# psas_c3_team05.net
KiCad netlist of a schematic drawn in EAGLE
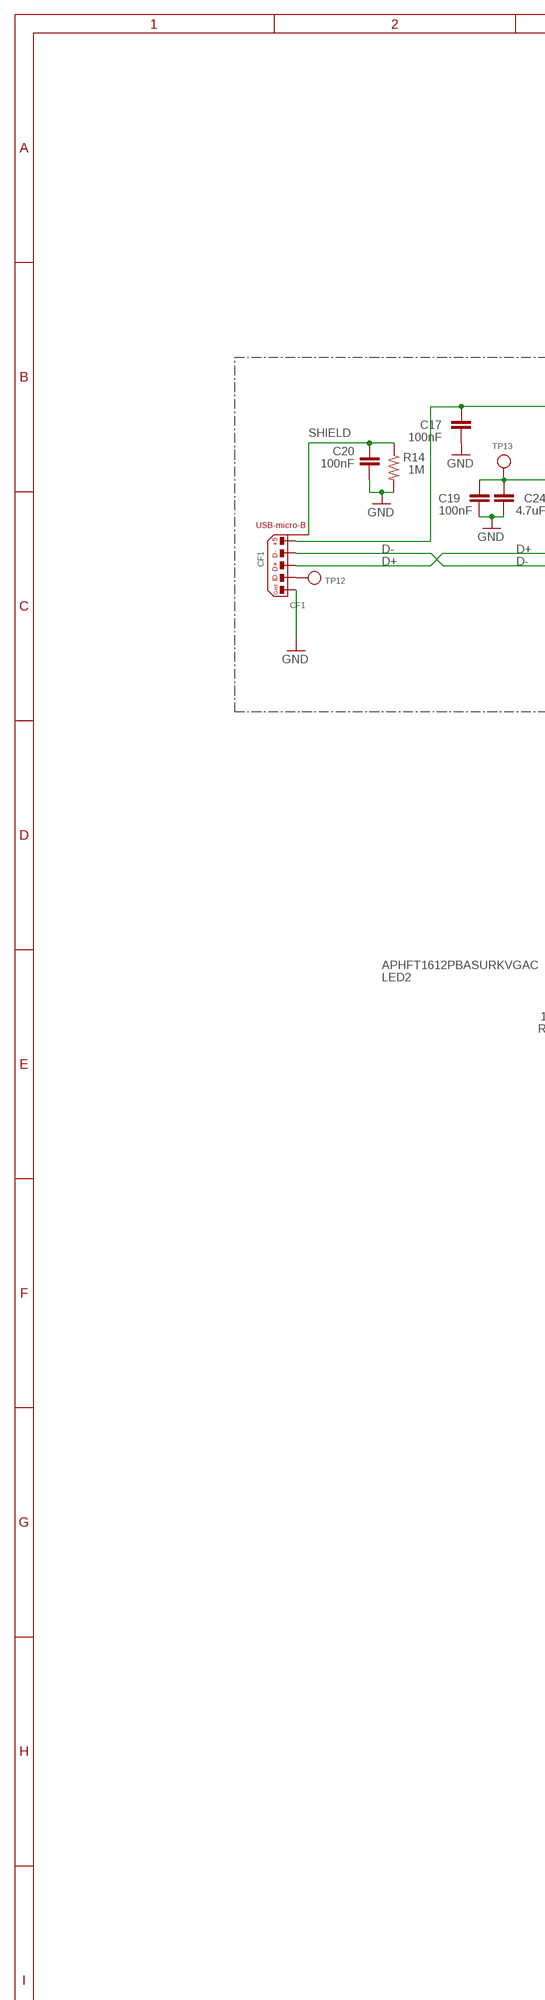
[diagram p0: schematic, sheet 1, part 1 of 2]
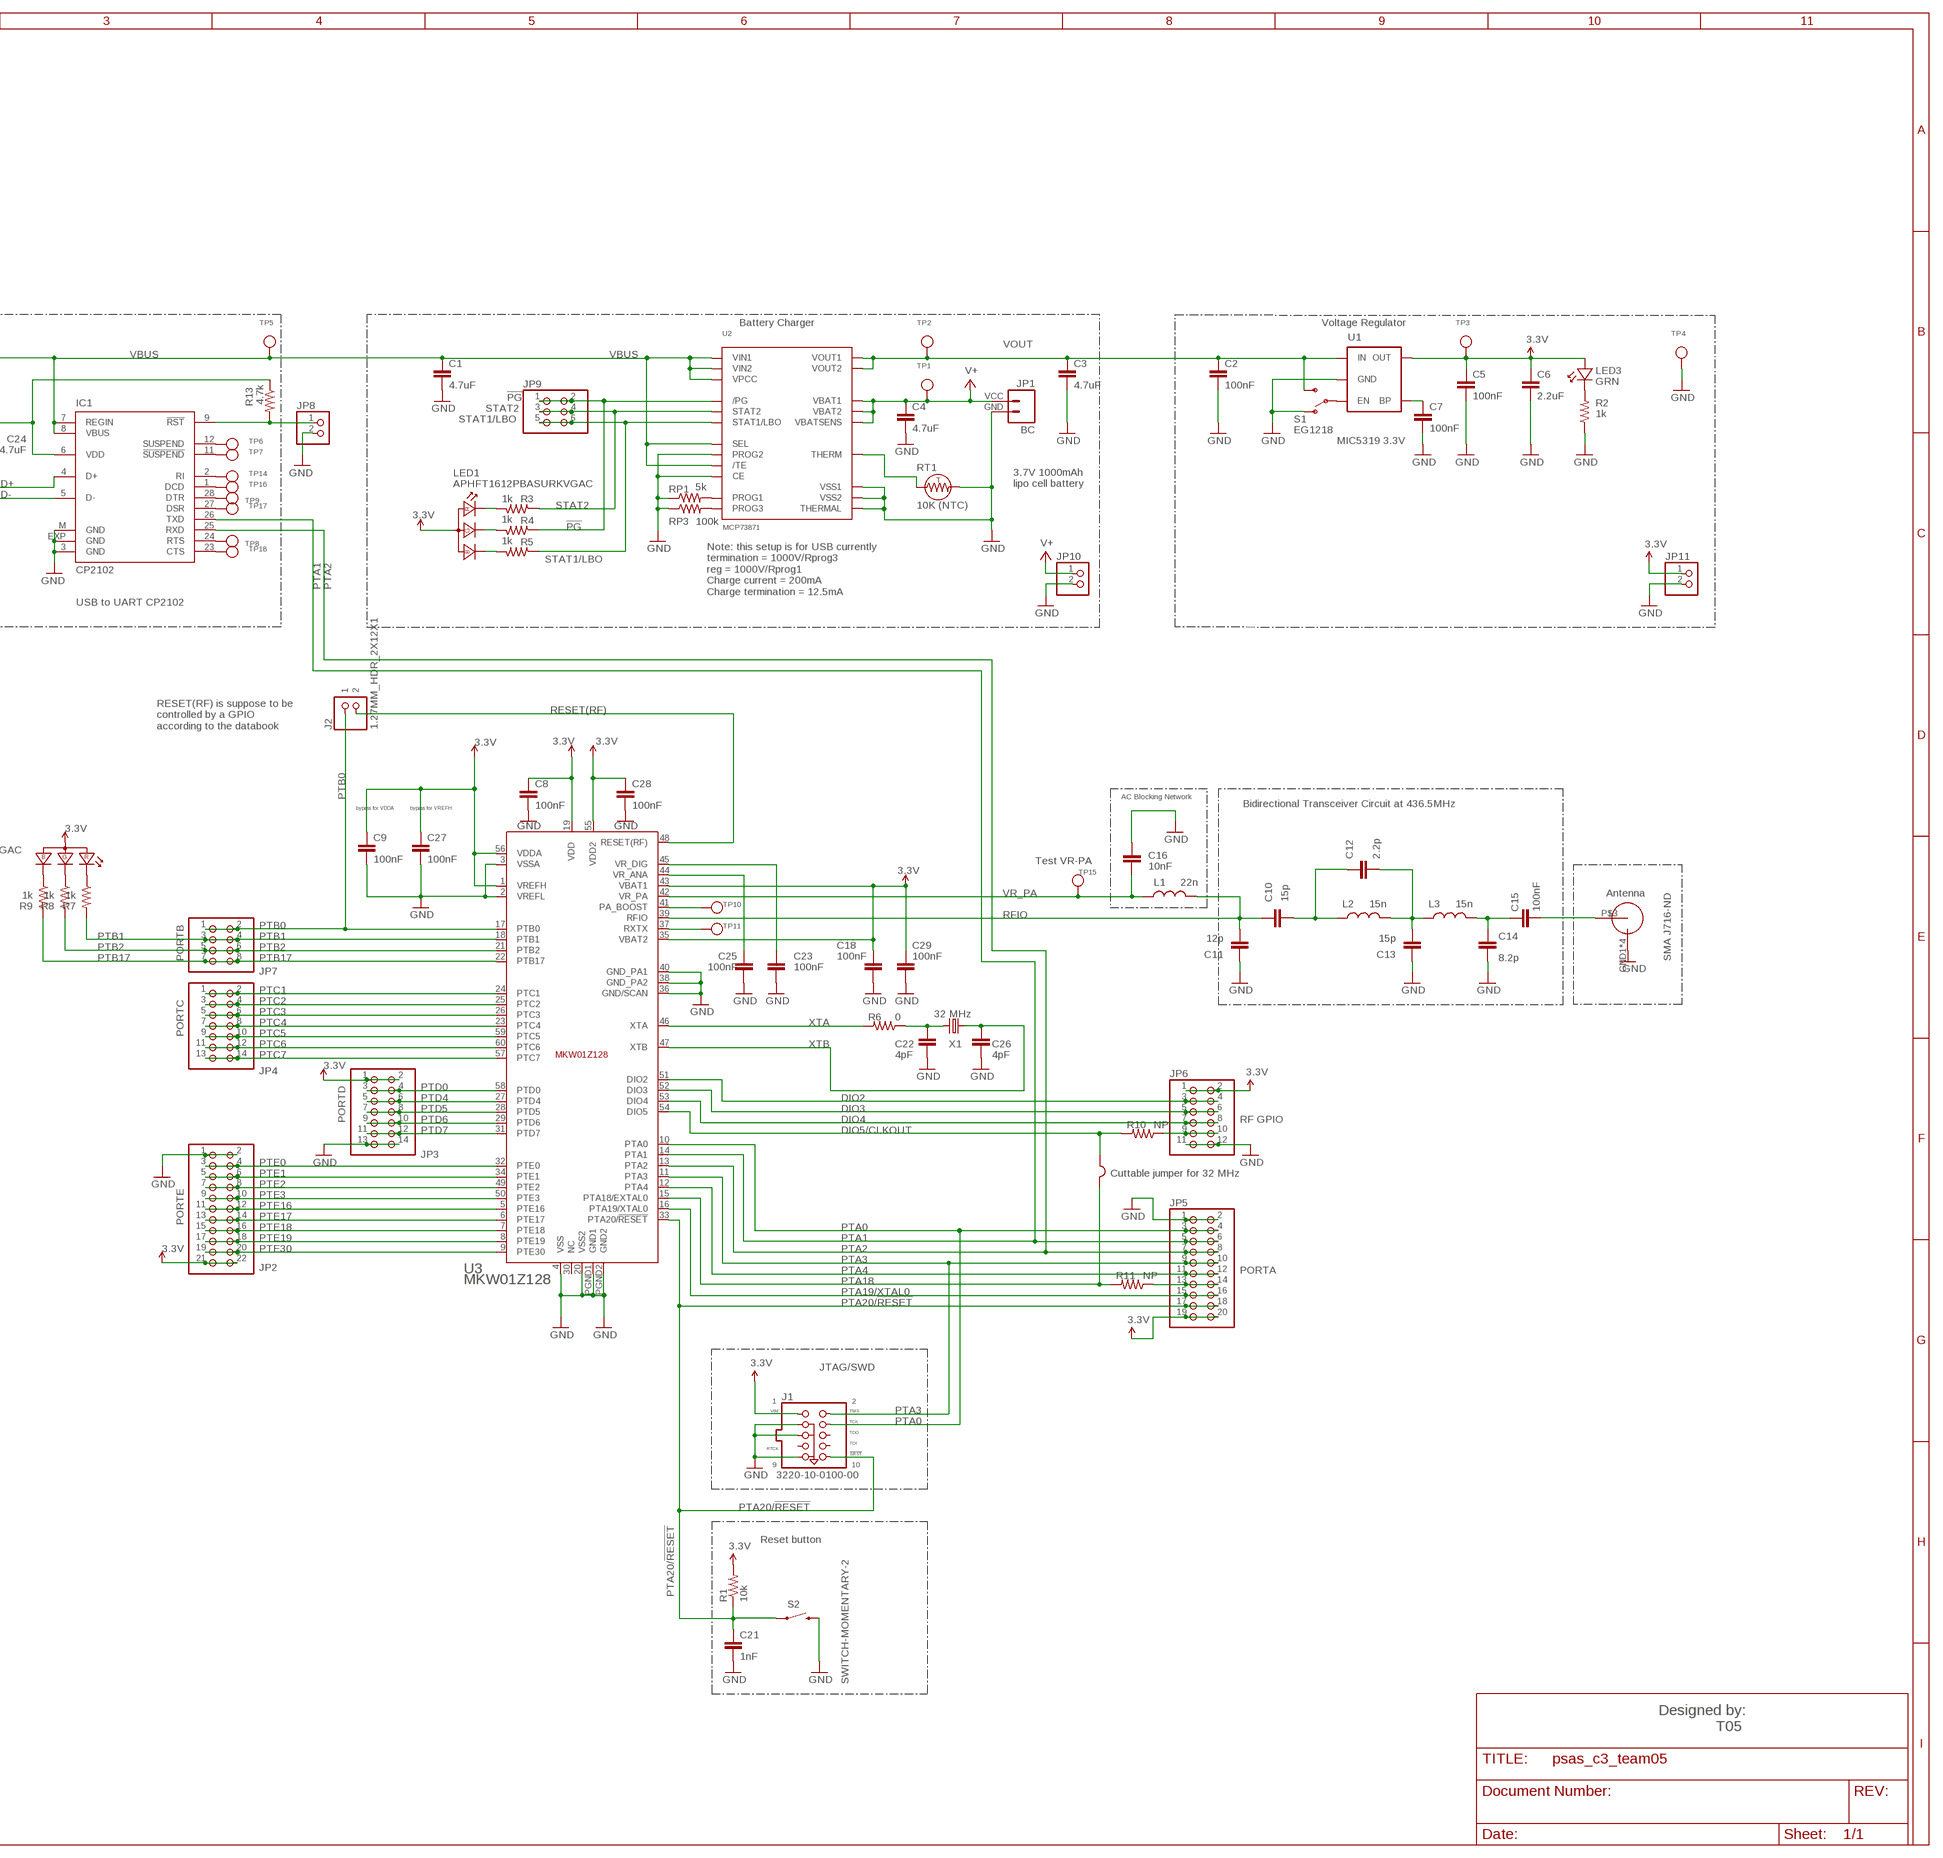
[diagram p1: schematic, sheet 1, part 2 of 2]

(export (version "E")
  (design (tool "Eeschema 10.0.6"))
  (components
    (comp (ref "C1")
      (value "4.7uF")
      (footprint "eagle-import:.0805-B-NOSILK")
      (fields (field (name "MFG") "Wurth Electronics Inc"))
      (libsource (lib "eagle-import") (part "rcl_custom_C-EU0805-B-NOSILK"))
    )
    (comp (ref "C2")
      (value "100nF")
      (footprint "eagle-import:.0603-B-NOSILK")
      (fields (field (name "MFG") "Murata Electronics North America"))
      (libsource (lib "eagle-import") (part "rcl_custom_C-EU0603-B-NOSILK"))
    )
    (comp (ref "C3")
      (value "4.7uF")
      (footprint "eagle-import:.0805-B-NOSILK")
      (fields (field (name "MFG") "Wurth Electronics Inc"))
      (libsource (lib "eagle-import") (part "rcl_custom_C-EU0805-B-NOSILK"))
    )
    (comp (ref "C4")
      (value "4.7uF")
      (footprint "eagle-import:.0805-B-NOSILK")
      (fields (field (name "MFG") "Wurth Electronics Inc"))
      (libsource (lib "eagle-import") (part "rcl_custom_C-EU0805-B-NOSILK"))
    )
    (comp (ref "C5")
      (value "100nF")
      (footprint "eagle-import:.0603-B-NOSILK")
      (fields (field (name "MFG") "Murata Electronics North America"))
      (libsource (lib "eagle-import") (part "rcl_custom_C-EU0603-B-NOSILK"))
    )
    (comp (ref "C6")
      (value "2.2uF")
      (footprint "eagle-import:.0805-B-NOSILK")
      (fields (field (name "MFG") "Murata Electronics North America"))
      (libsource (lib "eagle-import") (part "rcl_custom_C-EU0805-B-NOSILK"))
    )
    (comp (ref "C7")
      (value "100nF")
      (footprint "eagle-import:.0603-B-NOSILK")
      (fields (field (name "MFG") "Murata Electronics North America"))
      (libsource (lib "eagle-import") (part "rcl_custom_C-EU0603-B-NOSILK"))
    )
    (comp (ref "C8")
      (value "100nF")
      (footprint "eagle-import:.0603-B-NOSILK")
      (fields
        (field (name "MFG") "Murata Electronics North America")
        (field (name "MPN") "GRM188R71C104KA01D")
      )
      (libsource (lib "eagle-import") (part "C-EU0603-B-NOSILK"))
    )
    (comp (ref "C9")
      (value "100nF")
      (footprint "eagle-import:.0603-B-NOSILK")
      (fields
        (field (name "MFG") "Murata Electronics North America")
        (field (name "MPN") "GRM188R71C104KA01D")
      )
      (libsource (lib "eagle-import") (part "C-EU0603-B-NOSILK"))
    )
    (comp (ref "C10")
      (value "15p")
      (footprint "eagle-import:.0603-B-NOSILK")
      (fields (field (name "MFG") "AVX"))
      (libsource (lib "eagle-import") (part "rcl_custom_C-EU0603-B-NOSILK"))
    )
    (comp (ref "C11")
      (value "12p")
      (footprint "eagle-import:.0603-B-NOSILK")
      (fields (field (name "MFG") "AVX"))
      (libsource (lib "eagle-import") (part "rcl_custom_C-EU0603-B-NOSILK"))
    )
    (comp (ref "C12")
      (value "2.2p")
      (footprint "eagle-import:.0603-B-NOSILK")
      (fields (field (name "MFG") "Vishay / Vitramon"))
      (libsource (lib "eagle-import") (part "rcl_custom_C-EU0603-B-NOSILK"))
    )
    (comp (ref "C13")
      (value "15p")
      (footprint "eagle-import:.0603-B-NOSILK")
      (fields (field (name "MFG") "AVX"))
      (libsource (lib "eagle-import") (part "rcl_custom_C-EU0603-B-NOSILK"))
    )
    (comp (ref "C14")
      (value "8.2p")
      (footprint "eagle-import:.0603-B-NOSILK")
      (fields (field (name "MFG") "Johanson Technology"))
      (libsource (lib "eagle-import") (part "rcl_custom_C-EU0603-B-NOSILK"))
    )
    (comp (ref "C15")
      (value "100nF")
      (footprint "eagle-import:.0603-B-NOSILK")
      (fields (field (name "MFG") "AVX"))
      (libsource (lib "eagle-import") (part "rcl_custom_C-EU0603-B-NOSILK"))
    )
    (comp (ref "C16")
      (value "10nF")
      (footprint "eagle-import:.0603-B-NOSILK")
      (fields (field (name "MFG") "AVX"))
      (libsource (lib "eagle-import") (part "rcl_custom_C-EU0603-B-NOSILK"))
    )
    (comp (ref "C17")
      (value "100nF")
      (footprint "eagle-import:.0603-B-NOSILK")
      (fields (field (name "MFG") "Murata Electronics North America"))
      (libsource (lib "eagle-import") (part "rcl_custom_C-EU0603-B-NOSILK"))
    )
    (comp (ref "C18")
      (value "100nF")
      (footprint "eagle-import:.0603-B-NOSILK")
      (fields
        (field (name "MFG") "Murata Electronics North America")
        (field (name "MPN") "GRM188R71C104KA01D")
      )
      (libsource (lib "eagle-import") (part "C-EU0603-B-NOSILK"))
    )
    (comp (ref "C19")
      (value "100nF")
      (footprint "eagle-import:.0603-B-NOSILK")
      (fields (field (name "MFG") "Murata Electronics North America"))
      (libsource (lib "eagle-import") (part "rcl_custom_C-EU0603-B-NOSILK"))
    )
    (comp (ref "C20")
      (value "100nF")
      (footprint "eagle-import:.0603-B-NOSILK")
      (fields (field (name "MFG") "Murata Electronics North America"))
      (libsource (lib "eagle-import") (part "rcl_custom_C-EU0603-B-NOSILK"))
    )
    (comp (ref "C21")
      (value "1nF")
      (footprint "eagle-import:.0603-B-NOSILK")
      (fields (field (name "MFG") "Kemet"))
      (libsource (lib "eagle-import") (part "rcl_custom_C-EU0603-B-NOSILK"))
    )
    (comp (ref "C22")
      (value "4pF")
      (footprint "eagle-import:.0603-B-NOSILK")
      (fields
        (field (name "MFG") "Murata Electronics North America")
        (field (name "MPN") "GRM1885C1H4R0CA01D")
      )
      (libsource (lib "eagle-import") (part "C-EU0603-B-NOSILK"))
    )
    (comp (ref "C23")
      (value "100nF")
      (footprint "eagle-import:.0603-B-NOSILK")
      (fields
        (field (name "MFG") "Murata Electronics North America")
        (field (name "MPN") "GRM188R71C104KA01D")
      )
      (libsource (lib "eagle-import") (part "C-EU0603-B-NOSILK"))
    )
    (comp (ref "C24")
      (value "4.7uF")
      (footprint "eagle-import:.0805-B-NOSILK")
      (fields (field (name "MFG") "Wurth Electronics Inc"))
      (libsource (lib "eagle-import") (part "rcl_custom_C-EU0805-B-NOSILK"))
    )
    (comp (ref "C25")
      (value "100nF")
      (footprint "eagle-import:.0603-B-NOSILK")
      (fields
        (field (name "MFG") "Murata Electronics North America")
        (field (name "MPN") "GRM188R71C104KA01D")
      )
      (libsource (lib "eagle-import") (part "C-EU0603-B-NOSILK"))
    )
    (comp (ref "C26")
      (value "4pF")
      (footprint "eagle-import:.0603-B-NOSILK")
      (fields
        (field (name "MFG") "Murata Electronics North America")
        (field (name "MPN") "GRM1885C1H4R0CA01D")
      )
      (libsource (lib "eagle-import") (part "C-EU0603-B-NOSILK"))
    )
    (comp (ref "C27")
      (value "100nF")
      (footprint "eagle-import:.0603-B-NOSILK")
      (fields
        (field (name "MFG") "Murata Electronics North America")
        (field (name "MPN") "GRM188R71C104KA01D")
      )
      (libsource (lib "eagle-import") (part "C-EU0603-B-NOSILK"))
    )
    (comp (ref "C28")
      (value "100nF")
      (footprint "eagle-import:.0603-B-NOSILK")
      (fields
        (field (name "MFG") "Murata Electronics North America")
        (field (name "MPN") "GRM188R71C104KA01D")
      )
      (libsource (lib "eagle-import") (part "C-EU0603-B-NOSILK"))
    )
    (comp (ref "C29")
      (value "100nF")
      (footprint "eagle-import:.0603-B-NOSILK")
      (fields
        (field (name "MFG") "Murata Electronics North America")
        (field (name "MPN") "GRM188R71C104KA01D")
      )
      (libsource (lib "eagle-import") (part "C-EU0603-B-NOSILK"))
    )
    (comp (ref "CF1")
      (value "CF1")
      (footprint "eagle-import:USB-MICRO-B-PTH-HIROSE")
      (fields (field (name "MFG") "Hirose Electric Co Ltd"))
      (libsource (lib "eagle-import") (part "CON_USB-MICRO-B-RECEPTACLE-PTH-HIROSE-ZX62D-B-5P8"))
    )
    (comp (ref "IC1")
      (value "CP2102")
      (footprint "eagle-import:MLP28")
      (fields
        (field (name "MF") "FARNELL")
        (field (name "MPN") "CP2102-GM")
        (field (name "MFG") "Silicon Labs")
      )
      (libsource (lib "eagle-import") (part "CP2102"))
    )
    (comp (ref "J1")
      (value "3220-10-0100-00")
      (footprint "eagle-import:PINHEADER-2X5-0.05+POL+SILK")
      (fields (field (name "MFG") "CNC Tech"))
      (libsource (lib "eagle-import") (part "JTAG_ARM-10-50MIL"))
    )
    (comp (ref "J2")
      (value "1.27MM_HDR_2X12X1")
      (footprint "eagle-import:1.27MM_2X1")
      (libsource (lib "eagle-import") (part "1.27MM_HDR_2X12X1"))
    )
    (comp (ref "JP1")
      (value "BC")
      (footprint "eagle-import:SPARKFUN-CONNECTORS_JST-2-SMD-VERT")
      (fields (field (name "MFG") "JST Sales America Inc."))
      (libsource (lib "eagle-import") (part "SPARKFUN-CONNECTORS_M024UCON-15767"))
    )
    (comp (ref "JP2")
      (value "PINHD-2X11")
      (footprint "eagle-import:2X11")
      (libsource (lib "eagle-import") (part "PINHD-2X11"))
    )
    (comp (ref "JP3")
      (value "PINHD-2X7")
      (footprint "eagle-import:2X07")
      (libsource (lib "eagle-import") (part "PINHD-2X7"))
    )
    (comp (ref "JP4")
      (value "PINHD-2X7")
      (footprint "eagle-import:2X07")
      (libsource (lib "eagle-import") (part "PINHD-2X7"))
    )
    (comp (ref "JP5")
      (value "PINHD-2X10")
      (footprint "eagle-import:2X10")
      (libsource (lib "eagle-import") (part "PINHD-2X10"))
    )
    (comp (ref "JP6")
      (value "PINHD-2X6")
      (footprint "eagle-import:2X06")
      (libsource (lib "eagle-import") (part "PINHD-2X6"))
    )
    (comp (ref "JP7")
      (value "PINHD-2X4")
      (footprint "eagle-import:2X04")
      (libsource (lib "eagle-import") (part "PINHD-2X4"))
    )
    (comp (ref "JP8")
      (value "PINHD-1X2")
      (footprint "eagle-import:1X02")
      (libsource (lib "eagle-import") (part "PINHD-1X2"))
    )
    (comp (ref "JP9")
      (value "PINHD-2X3")
      (footprint "eagle-import:2X03")
      (libsource (lib "eagle-import") (part "PINHD-2X3"))
    )
    (comp (ref "JP10")
      (value "PINHD-1X2")
      (footprint "eagle-import:1X02")
      (libsource (lib "eagle-import") (part "PINHD-1X2"))
    )
    (comp (ref "JP11")
      (value "PINHD-1X2")
      (footprint "eagle-import:1X02")
      (libsource (lib "eagle-import") (part "PINHD-1X2"))
    )
    (comp (ref "L1")
      (value "22n")
      (footprint "eagle-import:.0603-B-NOSILK")
      (fields (field (name "MFG") "Murata"))
      (libsource (lib "eagle-import") (part "L-US0603-B-NOSILK"))
    )
    (comp (ref "L2")
      (value "15n")
      (footprint "eagle-import:.0603-B-NOSILK")
      (fields (field (name "MFG") "Murata"))
      (libsource (lib "eagle-import") (part "L-US0603-B-NOSILK"))
    )
    (comp (ref "L3")
      (value "15n")
      (footprint "eagle-import:.0603-B-NOSILK")
      (fields (field (name "MFG") "Murata"))
      (libsource (lib "eagle-import") (part "L-US0603-B-NOSILK"))
    )
    (comp (ref "LED1")
      (value "APHFT1612PBASURKVGAC")
      (footprint "eagle-import:KINGBRITE_RGBLED_1.6X1.26")
      (fields (field (name "MFG") "Lite-On Inc."))
      (libsource (lib "eagle-import") (part "LED_RGB_COMMON_ANODE-1.6X1.26"))
    )
    (comp (ref "LED2")
      (value "APHFT1612PBASURKVGAC")
      (footprint "eagle-import:KINGBRITE_RGBLED_1.6X1.26")
      (fields (field (name "MFG") "Lite-On Inc."))
      (libsource (lib "eagle-import") (part "LED_RGB_COMMON_ANODE-1.6X1.26"))
    )
    (comp (ref "LED3")
      (value "GRN")
      (footprint "eagle-import:LED-0603")
      (fields (field (name "MFG") "Lite-On Inc."))
      (libsource (lib "eagle-import") (part "LED-0603"))
    )
    (comp (ref "R1")
      (value "10k")
      (footprint "eagle-import:.0603-B-NOSILK")
      (fields (field (name "MFG") "Yageo"))
      (libsource (lib "eagle-import") (part "R-US_0603-B-NOSILK"))
    )
    (comp (ref "R2")
      (value "1k")
      (footprint "eagle-import:.0603-B-NOSILK")
      (fields (field (name "MFG") "Yageo"))
      (libsource (lib "eagle-import") (part "R-US_0603-B-NOSILK"))
    )
    (comp (ref "R3")
      (value "1k")
      (footprint "eagle-import:.0603-B-NOSILK")
      (fields (field (name "MFG") "Yageo"))
      (libsource (lib "eagle-import") (part "R-US_0603-B-NOSILK"))
    )
    (comp (ref "R4")
      (value "1k")
      (footprint "eagle-import:.0603-B-NOSILK")
      (fields (field (name "MFG") "Yageo"))
      (libsource (lib "eagle-import") (part "R-US_0603-B-NOSILK"))
    )
    (comp (ref "R5")
      (value "1k")
      (footprint "eagle-import:.0603-B-NOSILK")
      (fields (field (name "MFG") "Yageo"))
      (libsource (lib "eagle-import") (part "R-US_0603-B-NOSILK"))
    )
    (comp (ref "R6")
      (value "0")
      (footprint "eagle-import:.0603-B-NOSILK")
      (libsource (lib "eagle-import") (part "R-US_0603-B-NOSILK"))
    )
    (comp (ref "R7")
      (value "1k")
      (footprint "eagle-import:.0603-B-NOSILK")
      (fields (field (name "MFG") "Yageo"))
      (libsource (lib "eagle-import") (part "R-US_0603-B-NOSILK"))
    )
    (comp (ref "R8")
      (value "1k")
      (footprint "eagle-import:.0603-B-NOSILK")
      (fields (field (name "MFG") "Yageo"))
      (libsource (lib "eagle-import") (part "R-US_0603-B-NOSILK"))
    )
    (comp (ref "R9")
      (value "1k")
      (footprint "eagle-import:.0603-B-NOSILK")
      (fields (field (name "MFG") "Yageo"))
      (libsource (lib "eagle-import") (part "R-US_0603-B-NOSILK"))
    )
    (comp (ref "R10")
      (value "NP")
      (footprint "eagle-import:.0603-B-NOSILK")
      (libsource (lib "eagle-import") (part "R-US_0603-B-NOSILK"))
    )
    (comp (ref "R11")
      (value "NP")
      (footprint "eagle-import:.0603-B-NOSILK")
      (libsource (lib "eagle-import") (part "R-US_0603-B-NOSILK"))
    )
    (comp (ref "R13")
      (value "4.7k")
      (footprint "eagle-import:.0603-B-NOSILK")
      (fields (field (name "MFG") "Yageo"))
      (libsource (lib "eagle-import") (part "R-US_0603-B-NOSILK"))
    )
    (comp (ref "R14")
      (value "1M")
      (footprint "eagle-import:.0603-B-NOSILK")
      (fields (field (name "MFG") "Yageo"))
      (libsource (lib "eagle-import") (part "R-US_0603-B-NOSILK"))
    )
    (comp (ref "RP1")
      (value "5k")
      (footprint "eagle-import:.0603-B-NOSILK")
      (fields (field (name "MFG") "Yageo"))
      (libsource (lib "eagle-import") (part "R-US_0603-B-NOSILK"))
    )
    (comp (ref "RP3")
      (value "100k")
      (footprint "eagle-import:.0603-B-NOSILK")
      (fields (field (name "MFG") "Yageo"))
      (libsource (lib "eagle-import") (part "R-US_0603-B-NOSILK"))
    )
    (comp (ref "RT1")
      (value "10K (NTC)")
      (footprint "eagle-import:R1206")
      (fields (field (name "MFG") "Honeywell Sensing and Control"))
      (libsource (lib "eagle-import") (part "THERMISTOR-_1206"))
    )
    (comp (ref "S1")
      (value "EG1218")
      (footprint "eagle-import:SWITCH-SPDT")
      (fields (field (name "MFG") "E-Switch"))
      (libsource (lib "eagle-import") (part "SWITCH-SPSTPTH"))
    )
    (comp (ref "S2")
      (value "SWITCH-MOMENTARY-2")
      (footprint "eagle-import:TACTILE_SWITCH_TALL")
      (fields (field (name "MFG") "TE Connectivity Alcoswitch Switches"))
      (libsource (lib "eagle-import") (part "SWITCH-MOMENTARY-2"))
    )
    (comp (ref "TP1")
      (value "TESTPOINTROUND0.5MM")
      (footprint "eagle-import:TESTPOINT_ROUND_0.5MM")
      (libsource (lib "eagle-import") (part "TESTPOINTROUND0.5MM"))
    )
    (comp (ref "TP2")
      (value "TESTPOINTROUND0.5MM")
      (footprint "eagle-import:TESTPOINT_ROUND_0.5MM")
      (libsource (lib "eagle-import") (part "TESTPOINTROUND0.5MM"))
    )
    (comp (ref "TP3")
      (value "TESTPOINTROUND0.5MM")
      (footprint "eagle-import:TESTPOINT_ROUND_0.5MM")
      (libsource (lib "eagle-import") (part "TESTPOINTROUND0.5MM"))
    )
    (comp (ref "TP4")
      (value "TESTPOINTROUND0.5MM")
      (footprint "eagle-import:TESTPOINT_ROUND_0.5MM")
      (libsource (lib "eagle-import") (part "TESTPOINTROUND0.5MM"))
    )
    (comp (ref "TP5")
      (value "TESTPOINTROUND0.5MM")
      (footprint "eagle-import:TESTPOINT_ROUND_0.5MM")
      (libsource (lib "eagle-import") (part "TESTPOINTROUND0.5MM"))
    )
    (comp (ref "TP6")
      (value "TESTPOINTROUND0.5MM")
      (footprint "eagle-import:TESTPOINT_ROUND_0.5MM")
      (libsource (lib "eagle-import") (part "TESTPOINTROUND0.5MM"))
    )
    (comp (ref "TP7")
      (value "TESTPOINTROUND0.5MM")
      (footprint "eagle-import:TESTPOINT_ROUND_0.5MM")
      (libsource (lib "eagle-import") (part "TESTPOINTROUND0.5MM"))
    )
    (comp (ref "TP8")
      (value "TESTPOINTROUND0.5MM")
      (footprint "eagle-import:TESTPOINT_ROUND_0.5MM")
      (libsource (lib "eagle-import") (part "TESTPOINTROUND0.5MM"))
    )
    (comp (ref "TP9")
      (value "TESTPOINTROUND0.5MM")
      (footprint "eagle-import:TESTPOINT_ROUND_0.5MM")
      (libsource (lib "eagle-import") (part "TESTPOINTROUND0.5MM"))
    )
    (comp (ref "TP10")
      (value "TESTPOINTROUND0.5MM")
      (footprint "eagle-import:TESTPOINT_ROUND_0.5MM")
      (libsource (lib "eagle-import") (part "TESTPOINTROUND0.5MM"))
    )
    (comp (ref "TP11")
      (value "TESTPOINTROUND0.5MM")
      (footprint "eagle-import:TESTPOINT_ROUND_0.5MM")
      (libsource (lib "eagle-import") (part "TESTPOINTROUND0.5MM"))
    )
    (comp (ref "TP12")
      (value "TESTPOINTROUND0.5MM")
      (footprint "eagle-import:TESTPOINT_ROUND_0.5MM")
      (libsource (lib "eagle-import") (part "TESTPOINTROUND0.5MM"))
    )
    (comp (ref "TP13")
      (value "TESTPOINTROUND0.5MM")
      (footprint "eagle-import:TESTPOINT_ROUND_0.5MM")
      (libsource (lib "eagle-import") (part "TESTPOINTROUND0.5MM"))
    )
    (comp (ref "TP14")
      (value "TESTPOINTROUND0.5MM")
      (footprint "eagle-import:TESTPOINT_ROUND_0.5MM")
      (libsource (lib "eagle-import") (part "TESTPOINTROUND0.5MM"))
    )
    (comp (ref "TP15")
      (value "TESTPOINTROUND0.5MM")
      (footprint "eagle-import:TESTPOINT_ROUND_0.5MM")
      (libsource (lib "eagle-import") (part "TESTPOINTROUND0.5MM"))
    )
    (comp (ref "TP16")
      (value "TESTPOINTROUND0.5MM")
      (footprint "eagle-import:TESTPOINT_ROUND_0.5MM")
      (libsource (lib "eagle-import") (part "TESTPOINTROUND0.5MM"))
    )
    (comp (ref "TP17")
      (value "TESTPOINTROUND0.5MM")
      (footprint "eagle-import:TESTPOINT_ROUND_0.5MM")
      (libsource (lib "eagle-import") (part "TESTPOINTROUND0.5MM"))
    )
    (comp (ref "TP18")
      (value "TESTPOINTROUND0.5MM")
      (footprint "eagle-import:TESTPOINT_ROUND_0.5MM")
      (libsource (lib "eagle-import") (part "TESTPOINTROUND0.5MM"))
    )
    (comp (ref "U$2")
      (value "SMAJ716-ND")
      (footprint "eagle-import:SMAJ716-ND")
      (fields (field (name "MFG") "Cinch Connectivity Solutions"))
      (libsource (lib "eagle-import") (part "SMAJ716-ND"))
    )
    (comp (ref "U1")
      (value "MIC5319 3.3V")
      (footprint "eagle-import:SPARKFUN-POWERIC_SOT23-5")
      (fields (field (name "MFG") "Microchip Technology"))
      (libsource (lib "eagle-import") (part "SPARKFUN-POWERIC_V_REG_MIC52193.3V"))
    )
    (comp (ref "U2")
      (value "MCP73871")
      (footprint "eagle-import:QFN20_4MM")
      (fields (field (name "MFG") "Microchip Technology"))
      (libsource (lib "eagle-import") (part "MCP73871"))
    )
    (comp (ref "U3")
      (value "MKW01Z128")
      (footprint "eagle-import:MKW01Z128")
      (fields (field (name "MFG") "Freescale Semiconductor"))
      (libsource (lib "eagle-import") (part "MKW01Z128"))
    )
    (comp (ref "W1")
      (value "CONNECTION-0.4")
      (footprint "eagle-import:CONNECTION-BUTT-0.4")
      (libsource (lib "eagle-import") (part "CONNECTION-0.4"))
    )
    (comp (ref "X1")
      (value "32 MHz")
      (footprint "eagle-import:FC-12M")
      (fields (field (name "MFG") "AVX Corp/Kyocera Corp"))
      (libsource (lib "eagle-import") (part "FC-12M"))
    )
  )
  (nets
    (net (code "1") (name "/D+") (class "Default")
      (node (ref "CF1") (pin "3") (pinfunction "3_3") (pintype "passive"))
      (node (ref "IC1") (pin "4") (pinfunction "D+_4") (pintype "bidirectional"))
    )
    (net (code "2") (name "/D-") (class "Default")
      (node (ref "CF1") (pin "2") (pinfunction "2_2") (pintype "passive"))
      (node (ref "IC1") (pin "5") (pinfunction "D-_5") (pintype "bidirectional"))
    )
    (net (code "3") (name "/DIO2") (class "Default")
      (node (ref "JP6") (pin "3") (pinfunction "3_3") (pintype "passive"))
      (node (ref "JP6") (pin "4") (pinfunction "4_4") (pintype "passive"))
      (node (ref "U3") (pin "51") (pinfunction "DIO2_51") (pintype "bidirectional"))
    )
    (net (code "4") (name "/DIO3") (class "Default")
      (node (ref "JP6") (pin "5") (pinfunction "5_5") (pintype "passive"))
      (node (ref "JP6") (pin "6") (pinfunction "6_6") (pintype "passive"))
      (node (ref "U3") (pin "52") (pinfunction "DIO3_52") (pintype "bidirectional"))
    )
    (net (code "5") (name "/DIO4") (class "Default")
      (node (ref "JP6") (pin "7") (pinfunction "7_7") (pintype "passive"))
      (node (ref "JP6") (pin "8") (pinfunction "8_8") (pintype "passive"))
      (node (ref "U3") (pin "53") (pinfunction "DIO4_53") (pintype "bidirectional"))
    )
    (net (code "6") (name "/DIO5{slash}CLKOUT") (class "Default")
      (node (ref "R10") (pin "2") (pinfunction "2_2") (pintype "passive"))
      (node (ref "U3") (pin "54") (pinfunction "DIO5_54") (pintype "bidirectional"))
      (node (ref "W1") (pin "P1") (pinfunction "1_P1") (pintype "passive"))
    )
    (net (code "7") (name "/PTA0") (class "Default")
      (node (ref "J1") (pin "4") (pinfunction "TCK_4") (pintype "passive"))
      (node (ref "JP5") (pin "3") (pinfunction "3_3") (pintype "passive"))
      (node (ref "JP5") (pin "4") (pinfunction "4_4") (pintype "passive"))
      (node (ref "U3") (pin "10") (pinfunction "PTA0_10") (pintype "bidirectional"))
    )
    (net (code "8") (name "/PTA1") (class "Default")
      (node (ref "IC1") (pin "26") (pinfunction "TXD_26") (pintype "output"))
      (node (ref "JP5") (pin "5") (pinfunction "5_5") (pintype "passive"))
      (node (ref "JP5") (pin "6") (pinfunction "6_6") (pintype "passive"))
      (node (ref "U3") (pin "14") (pinfunction "PTA1_14") (pintype "bidirectional"))
    )
    (net (code "9") (name "/PTA2") (class "Default")
      (node (ref "IC1") (pin "25") (pinfunction "RXD_25") (pintype "input"))
      (node (ref "JP5") (pin "7") (pinfunction "7_7") (pintype "passive"))
      (node (ref "JP5") (pin "8") (pinfunction "8_8") (pintype "passive"))
      (node (ref "U3") (pin "13") (pinfunction "PTA2_13") (pintype "bidirectional"))
    )
    (net (code "10") (name "/PTA3") (class "Default")
      (node (ref "J1") (pin "2") (pinfunction "TMS_2") (pintype "passive"))
      (node (ref "JP5") (pin "10") (pinfunction "10_10") (pintype "passive"))
      (node (ref "JP5") (pin "9") (pinfunction "9_9") (pintype "passive"))
      (node (ref "U3") (pin "11") (pinfunction "PTA3_11") (pintype "bidirectional"))
    )
    (net (code "11") (name "/PTA4") (class "Default")
      (node (ref "JP5") (pin "11") (pinfunction "11_11") (pintype "passive"))
      (node (ref "JP5") (pin "12") (pinfunction "12_12") (pintype "passive"))
      (node (ref "U3") (pin "12") (pinfunction "PTA4_12") (pintype "bidirectional"))
    )
    (net (code "12") (name "/PTA18") (class "Default")
      (node (ref "R11") (pin "2") (pinfunction "2_2") (pintype "passive"))
      (node (ref "U3") (pin "15") (pinfunction "PTA18/EXTAL0_15") (pintype "bidirectional"))
      (node (ref "W1") (pin "P2") (pinfunction "2_P2") (pintype "passive"))
    )
    (net (code "13") (name "/PTA19{slash}XTAL0") (class "Default")
      (node (ref "JP5") (pin "15") (pinfunction "15_15") (pintype "passive"))
      (node (ref "JP5") (pin "16") (pinfunction "16_16") (pintype "passive"))
      (node (ref "U3") (pin "16") (pinfunction "PTA19/XTAL0_16") (pintype "bidirectional"))
    )
    (net (code "14") (name "/PTA20{slash}~{RESET}") (class "Default")
      (node (ref "C21") (pin "1") (pinfunction "1_1") (pintype "passive"))
      (node (ref "J1") (pin "10") (pinfunction "SRST_10") (pintype "passive"))
      (node (ref "JP5") (pin "17") (pinfunction "17_17") (pintype "passive"))
      (node (ref "JP5") (pin "18") (pinfunction "18_18") (pintype "passive"))
      (node (ref "R1") (pin "1") (pinfunction "1_1") (pintype "passive"))
      (node (ref "S2") (pin "A2") (pinfunction "1_A2") (pintype "passive"))
      (node (ref "U3") (pin "33") (pinfunction "PTA20/~{RESET}_33") (pintype "bidirectional"))
    )
    (net (code "15") (name "/PTB0") (class "Default")
      (node (ref "J2") (pin "1") (pinfunction "1_1") (pintype "passive"))
      (node (ref "JP7") (pin "1") (pinfunction "1_1") (pintype "passive"))
      (node (ref "JP7") (pin "2") (pinfunction "2_2") (pintype "passive"))
      (node (ref "U3") (pin "17") (pinfunction "PTB0_17") (pintype "bidirectional"))
    )
    (net (code "16") (name "/PTB1") (class "Default")
      (node (ref "JP7") (pin "3") (pinfunction "3_3") (pintype "passive"))
      (node (ref "JP7") (pin "4") (pinfunction "4_4") (pintype "passive"))
      (node (ref "R7") (pin "2") (pinfunction "2_2") (pintype "passive"))
      (node (ref "U3") (pin "18") (pinfunction "PTB1_18") (pintype "bidirectional"))
    )
    (net (code "17") (name "/PTB2") (class "Default")
      (node (ref "JP7") (pin "5") (pinfunction "5_5") (pintype "passive"))
      (node (ref "JP7") (pin "6") (pinfunction "6_6") (pintype "passive"))
      (node (ref "R8") (pin "2") (pinfunction "2_2") (pintype "passive"))
      (node (ref "U3") (pin "21") (pinfunction "PTB2_21") (pintype "bidirectional"))
    )
    (net (code "18") (name "/PTB17") (class "Default")
      (node (ref "JP7") (pin "7") (pinfunction "7_7") (pintype "passive"))
      (node (ref "JP7") (pin "8") (pinfunction "8_8") (pintype "passive"))
      (node (ref "R9") (pin "2") (pinfunction "2_2") (pintype "passive"))
      (node (ref "U3") (pin "22") (pinfunction "PTB17_22") (pintype "bidirectional"))
    )
    (net (code "19") (name "/PTC1") (class "Default")
      (node (ref "JP4") (pin "1") (pinfunction "1_1") (pintype "passive"))
      (node (ref "JP4") (pin "2") (pinfunction "2_2") (pintype "passive"))
      (node (ref "U3") (pin "24") (pinfunction "PTC1_24") (pintype "bidirectional"))
    )
    (net (code "20") (name "/PTC2") (class "Default")
      (node (ref "JP4") (pin "3") (pinfunction "3_3") (pintype "passive"))
      (node (ref "JP4") (pin "4") (pinfunction "4_4") (pintype "passive"))
      (node (ref "U3") (pin "25") (pinfunction "PTC2_25") (pintype "bidirectional"))
    )
    (net (code "21") (name "/PTC3") (class "Default")
      (node (ref "JP4") (pin "5") (pinfunction "5_5") (pintype "passive"))
      (node (ref "JP4") (pin "6") (pinfunction "6_6") (pintype "passive"))
      (node (ref "U3") (pin "26") (pinfunction "PTC3_26") (pintype "bidirectional"))
    )
    (net (code "22") (name "/PTC4") (class "Default")
      (node (ref "JP4") (pin "7") (pinfunction "7_7") (pintype "passive"))
      (node (ref "JP4") (pin "8") (pinfunction "8_8") (pintype "passive"))
      (node (ref "U3") (pin "23") (pinfunction "PTC4_23") (pintype "bidirectional"))
    )
    (net (code "23") (name "/PTC5") (class "Default")
      (node (ref "JP4") (pin "10") (pinfunction "10_10") (pintype "passive"))
      (node (ref "JP4") (pin "9") (pinfunction "9_9") (pintype "passive"))
      (node (ref "U3") (pin "59") (pinfunction "PTC5_59") (pintype "bidirectional"))
    )
    (net (code "24") (name "/PTC6") (class "Default")
      (node (ref "JP4") (pin "11") (pinfunction "11_11") (pintype "passive"))
      (node (ref "JP4") (pin "12") (pinfunction "12_12") (pintype "passive"))
      (node (ref "U3") (pin "60") (pinfunction "PTC6_60") (pintype "bidirectional"))
    )
    (net (code "25") (name "/PTC7") (class "Default")
      (node (ref "JP4") (pin "13") (pinfunction "13_13") (pintype "passive"))
      (node (ref "JP4") (pin "14") (pinfunction "14_14") (pintype "passive"))
      (node (ref "U3") (pin "57") (pinfunction "PTC7_57") (pintype "bidirectional"))
    )
    (net (code "26") (name "/PTD0") (class "Default")
      (node (ref "JP3") (pin "3") (pinfunction "3_3") (pintype "passive"))
      (node (ref "JP3") (pin "4") (pinfunction "4_4") (pintype "passive"))
      (node (ref "U3") (pin "58") (pinfunction "PTD0_58") (pintype "bidirectional"))
    )
    (net (code "27") (name "/PTD4") (class "Default")
      (node (ref "JP3") (pin "5") (pinfunction "5_5") (pintype "passive"))
      (node (ref "JP3") (pin "6") (pinfunction "6_6") (pintype "passive"))
      (node (ref "U3") (pin "27") (pinfunction "PTD4_27") (pintype "bidirectional"))
    )
    (net (code "28") (name "/PTD5") (class "Default")
      (node (ref "JP3") (pin "7") (pinfunction "7_7") (pintype "passive"))
      (node (ref "JP3") (pin "8") (pinfunction "8_8") (pintype "passive"))
      (node (ref "U3") (pin "28") (pinfunction "PTD5_28") (pintype "bidirectional"))
    )
    (net (code "29") (name "/PTD6") (class "Default")
      (node (ref "JP3") (pin "10") (pinfunction "10_10") (pintype "passive"))
      (node (ref "JP3") (pin "9") (pinfunction "9_9") (pintype "passive"))
      (node (ref "U3") (pin "29") (pinfunction "PTD6_29") (pintype "bidirectional"))
    )
    (net (code "30") (name "/PTD7") (class "Default")
      (node (ref "JP3") (pin "11") (pinfunction "11_11") (pintype "passive"))
      (node (ref "JP3") (pin "12") (pinfunction "12_12") (pintype "passive"))
      (node (ref "U3") (pin "31") (pinfunction "PTD7_31") (pintype "bidirectional"))
    )
    (net (code "31") (name "/PTE0") (class "Default")
      (node (ref "JP2") (pin "3") (pinfunction "3_3") (pintype "passive"))
      (node (ref "JP2") (pin "4") (pinfunction "4_4") (pintype "passive"))
      (node (ref "U3") (pin "32") (pinfunction "PTE0_32") (pintype "bidirectional"))
    )
    (net (code "32") (name "/PTE1") (class "Default")
      (node (ref "JP2") (pin "5") (pinfunction "5_5") (pintype "passive"))
      (node (ref "JP2") (pin "6") (pinfunction "6_6") (pintype "passive"))
      (node (ref "U3") (pin "34") (pinfunction "PTE1_34") (pintype "bidirectional"))
    )
    (net (code "33") (name "/PTE2") (class "Default")
      (node (ref "JP2") (pin "7") (pinfunction "7_7") (pintype "passive"))
      (node (ref "JP2") (pin "8") (pinfunction "8_8") (pintype "passive"))
      (node (ref "U3") (pin "49") (pinfunction "PTE2_49") (pintype "bidirectional"))
    )
    (net (code "34") (name "/PTE3") (class "Default")
      (node (ref "JP2") (pin "10") (pinfunction "10_10") (pintype "passive"))
      (node (ref "JP2") (pin "9") (pinfunction "9_9") (pintype "passive"))
      (node (ref "U3") (pin "50") (pinfunction "PTE3_50") (pintype "bidirectional"))
    )
    (net (code "35") (name "/PTE16") (class "Default")
      (node (ref "JP2") (pin "11") (pinfunction "11_11") (pintype "passive"))
      (node (ref "JP2") (pin "12") (pinfunction "12_12") (pintype "passive"))
      (node (ref "U3") (pin "5") (pinfunction "PTE16_5") (pintype "bidirectional"))
    )
    (net (code "36") (name "/PTE17") (class "Default")
      (node (ref "JP2") (pin "13") (pinfunction "13_13") (pintype "passive"))
      (node (ref "JP2") (pin "14") (pinfunction "14_14") (pintype "passive"))
      (node (ref "U3") (pin "6") (pinfunction "PTE17_6") (pintype "bidirectional"))
    )
    (net (code "37") (name "/PTE18") (class "Default")
      (node (ref "JP2") (pin "15") (pinfunction "15_15") (pintype "passive"))
      (node (ref "JP2") (pin "16") (pinfunction "16_16") (pintype "passive"))
      (node (ref "U3") (pin "7") (pinfunction "PTE18_7") (pintype "bidirectional"))
    )
    (net (code "38") (name "/PTE19") (class "Default")
      (node (ref "JP2") (pin "17") (pinfunction "17_17") (pintype "passive"))
      (node (ref "JP2") (pin "18") (pinfunction "18_18") (pintype "passive"))
      (node (ref "U3") (pin "8") (pinfunction "PTE19_8") (pintype "bidirectional"))
    )
    (net (code "39") (name "/PTE30") (class "Default")
      (node (ref "JP2") (pin "19") (pinfunction "19_19") (pintype "passive"))
      (node (ref "JP2") (pin "20") (pinfunction "20_20") (pintype "passive"))
      (node (ref "U3") (pin "9") (pinfunction "PTE30_9") (pintype "bidirectional"))
    )
    (net (code "40") (name "/RESET(RF)") (class "Default")
      (node (ref "J2") (pin "2") (pinfunction "2_2") (pintype "passive"))
      (node (ref "U3") (pin "48") (pinfunction "RESET(RF)_48") (pintype "input"))
    )
    (net (code "41") (name "/RFIO") (class "Default")
      (node (ref "C10") (pin "2") (pinfunction "2_2") (pintype "passive"))
      (node (ref "C11") (pin "1") (pinfunction "1_1") (pintype "passive"))
      (node (ref "L1") (pin "2") (pinfunction "2_2") (pintype "passive"))
      (node (ref "U3") (pin "39") (pinfunction "RFIO_39") (pintype "bidirectional"))
    )
    (net (code "42") (name "/SHIELD") (class "Default")
      (node (ref "C20") (pin "1") (pinfunction "1_1") (pintype "passive"))
      (node (ref "CF1") (pin "S1") (pinfunction "SHIELD_S1") (pintype "passive"))
      (node (ref "CF1") (pin "S2") (pinfunction "SHIELD_S2") (pintype "passive"))
      (node (ref "CF1") (pin "S3") (pinfunction "SHIELD_S3") (pintype "passive"))
      (node (ref "CF1") (pin "S4") (pinfunction "SHIELD_S4") (pintype "passive"))
      (node (ref "R14") (pin "1") (pinfunction "1_1") (pintype "passive"))
    )
    (net (code "43") (name "/STAT1{slash}LBO") (class "Default")
      (node (ref "JP9") (pin "5") (pinfunction "5_5") (pintype "passive"))
      (node (ref "JP9") (pin "6") (pinfunction "6_6") (pintype "passive"))
      (node (ref "R5") (pin "1") (pinfunction "1_1") (pintype "passive"))
      (node (ref "U2") (pin "P$8") (pinfunction "STAT1/LBO_P$8") (pintype "output"))
    )
    (net (code "44") (name "/STAT2") (class "Default")
      (node (ref "JP9") (pin "3") (pinfunction "3_3") (pintype "passive"))
      (node (ref "JP9") (pin "4") (pinfunction "4_4") (pintype "passive"))
      (node (ref "R3") (pin "1") (pinfunction "1_1") (pintype "passive"))
      (node (ref "U2") (pin "P$7") (pinfunction "STAT2_P$7") (pintype "output"))
    )
    (net (code "45") (name "/VBUS") (class "Default")
      (node (ref "C1") (pin "1") (pinfunction "1_1") (pintype "passive"))
      (node (ref "C17") (pin "1") (pinfunction "1_1") (pintype "passive"))
      (node (ref "CF1") (pin "1") (pinfunction "1_1") (pintype "passive"))
      (node (ref "IC1") (pin "7") (pinfunction "REGIN_7") (pintype "passive"))
      (node (ref "IC1") (pin "8") (pinfunction "VBUS_8") (pintype "input"))
      (node (ref "TP5") (pin "P$1") (pinfunction "P$1_P$1") (pintype "bidirectional"))
      (node (ref "U2") (pin "P$18") (pinfunction "VIN1_P$18") (pintype "power_in"))
      (node (ref "U2") (pin "P$19") (pinfunction "VIN2_P$19") (pintype "power_in"))
      (node (ref "U2") (pin "P$2") (pinfunction "VPCC_P$2") (pintype "passive"))
      (node (ref "U2") (pin "P$3") (pinfunction "SEL_P$3") (pintype "input"))
      (node (ref "U2") (pin "P$9") (pinfunction "/TE_P$9") (pintype "input"))
    )
    (net (code "46") (name "/VOUT") (class "Default")
      (node (ref "C2") (pin "1") (pinfunction "1_1") (pintype "passive"))
      (node (ref "C3") (pin "1") (pinfunction "1_1") (pintype "passive"))
      (node (ref "S1") (pin "3") (pinfunction "S_3") (pintype "passive"))
      (node (ref "TP2") (pin "P$1") (pinfunction "P$1_P$1") (pintype "bidirectional"))
      (node (ref "U1") (pin "1") (pinfunction "IN_1") (pintype "input"))
      (node (ref "U2") (pin "P$1") (pinfunction "VOUT1_P$1") (pintype "power_in"))
      (node (ref "U2") (pin "P$20") (pinfunction "VOUT2_P$20") (pintype "power_in"))
    )
    (net (code "47") (name "/VR_PA") (class "Default")
      (node (ref "C16") (pin "2") (pinfunction "2_2") (pintype "passive"))
      (node (ref "L1") (pin "1") (pinfunction "1_1") (pintype "passive"))
      (node (ref "TP15") (pin "P$1") (pinfunction "P$1_P$1") (pintype "bidirectional"))
      (node (ref "U3") (pin "42") (pinfunction "VR_PA_42") (pintype "output"))
    )
    (net (code "48") (name "/XTA") (class "Default")
      (node (ref "R6") (pin "2") (pinfunction "2_2") (pintype "passive"))
      (node (ref "U3") (pin "46") (pinfunction "XTA_46") (pintype "passive"))
    )
    (net (code "49") (name "/XTB") (class "Default")
      (node (ref "C26") (pin "1") (pinfunction "1_1") (pintype "passive"))
      (node (ref "U3") (pin "47") (pinfunction "XTB_47") (pintype "passive"))
      (node (ref "X1") (pin "1") (pinfunction "1_1") (pintype "passive"))
    )
    (net (code "50") (name "/~{PG}") (class "Default")
      (node (ref "JP9") (pin "1") (pinfunction "1_1") (pintype "passive"))
      (node (ref "JP9") (pin "2") (pinfunction "2_2") (pintype "passive"))
      (node (ref "R4") (pin "1") (pinfunction "1_1") (pintype "passive"))
      (node (ref "U2") (pin "P$6") (pinfunction "/PG_P$6") (pintype "output"))
    )
    (net (code "51") (name "3.3V") (class "Default")
      (node (ref "C18") (pin "1") (pinfunction "1_1") (pintype "passive"))
      (node (ref "C27") (pin "1") (pinfunction "1_1") (pintype "passive"))
      (node (ref "C28") (pin "1") (pinfunction "1_1") (pintype "passive"))
      (node (ref "C29") (pin "1") (pinfunction "1_1") (pintype "passive"))
      (node (ref "C5") (pin "1") (pinfunction "1_1") (pintype "passive"))
      (node (ref "C6") (pin "1") (pinfunction "1_1") (pintype "passive"))
      (node (ref "C8") (pin "1") (pinfunction "1_1") (pintype "passive"))
      (node (ref "C9") (pin "1") (pinfunction "1_1") (pintype "passive"))
      (node (ref "J1") (pin "1") (pinfunction "VDD_1") (pintype "passive"))
      (node (ref "JP11") (pin "1") (pinfunction "1_1") (pintype "passive"))
      (node (ref "JP2") (pin "21") (pinfunction "21_21") (pintype "passive"))
      (node (ref "JP2") (pin "22") (pinfunction "22_22") (pintype "passive"))
      (node (ref "JP3") (pin "1") (pinfunction "1_1") (pintype "passive"))
      (node (ref "JP3") (pin "2") (pinfunction "2_2") (pintype "passive"))
      (node (ref "JP5") (pin "19") (pinfunction "19_19") (pintype "passive"))
      (node (ref "JP5") (pin "20") (pinfunction "20_20") (pintype "passive"))
      (node (ref "JP6") (pin "1") (pinfunction "1_1") (pintype "passive"))
      (node (ref "JP6") (pin "2") (pinfunction "2_2") (pintype "passive"))
      (node (ref "LED1") (pin "2") (pinfunction "COMMON_ANODE_2") (pintype "passive"))
      (node (ref "LED2") (pin "2") (pinfunction "COMMON_ANODE_2") (pintype "passive"))
      (node (ref "LED3") (pin "A") (pinfunction "A_A") (pintype "passive"))
      (node (ref "R1") (pin "2") (pinfunction "2_2") (pintype "passive"))
      (node (ref "TP3") (pin "P$1") (pinfunction "P$1_P$1") (pintype "bidirectional"))
      (node (ref "U1") (pin "5") (pinfunction "OUT_5") (pintype "passive"))
      (node (ref "U3") (pin "1") (pinfunction "VREFH_1") (pintype "input"))
      (node (ref "U3") (pin "19") (pinfunction "VDD_19") (pintype "power_in"))
      (node (ref "U3") (pin "35") (pinfunction "VBAT2_35") (pintype "power_in"))
      (node (ref "U3") (pin "43") (pinfunction "VBAT1_43") (pintype "power_in"))
      (node (ref "U3") (pin "55") (pinfunction "VDD2_55") (pintype "power_in"))
      (node (ref "U3") (pin "56") (pinfunction "VDDA_56") (pintype "power_in"))
    )
    (net (code "52") (name "GND") (class "Default")
      (node (ref "C1") (pin "2") (pinfunction "2_2") (pintype "passive"))
      (node (ref "C11") (pin "2") (pinfunction "2_2") (pintype "passive"))
      (node (ref "C13") (pin "2") (pinfunction "2_2") (pintype "passive"))
      (node (ref "C14") (pin "2") (pinfunction "2_2") (pintype "passive"))
      (node (ref "C16") (pin "1") (pinfunction "1_1") (pintype "passive"))
      (node (ref "C17") (pin "2") (pinfunction "2_2") (pintype "passive"))
      (node (ref "C18") (pin "2") (pinfunction "2_2") (pintype "passive"))
      (node (ref "C19") (pin "2") (pinfunction "2_2") (pintype "passive"))
      (node (ref "C2") (pin "2") (pinfunction "2_2") (pintype "passive"))
      (node (ref "C20") (pin "2") (pinfunction "2_2") (pintype "passive"))
      (node (ref "C21") (pin "2") (pinfunction "2_2") (pintype "passive"))
      (node (ref "C22") (pin "2") (pinfunction "2_2") (pintype "passive"))
      (node (ref "C23") (pin "2") (pinfunction "2_2") (pintype "passive"))
      (node (ref "C24") (pin "2") (pinfunction "2_2") (pintype "passive"))
      (node (ref "C25") (pin "2") (pinfunction "2_2") (pintype "passive"))
      (node (ref "C26") (pin "2") (pinfunction "2_2") (pintype "passive"))
      (node (ref "C27") (pin "2") (pinfunction "2_2") (pintype "passive"))
      (node (ref "C28") (pin "2") (pinfunction "2_2") (pintype "passive"))
      (node (ref "C29") (pin "2") (pinfunction "2_2") (pintype "passive"))
      (node (ref "C3") (pin "2") (pinfunction "2_2") (pintype "passive"))
      (node (ref "C4") (pin "2") (pinfunction "2_2") (pintype "passive"))
      (node (ref "C5") (pin "2") (pinfunction "2_2") (pintype "passive"))
      (node (ref "C6") (pin "2") (pinfunction "2_2") (pintype "passive"))
      (node (ref "C7") (pin "2") (pinfunction "2_2") (pintype "passive"))
      (node (ref "C8") (pin "2") (pinfunction "2_2") (pintype "passive"))
      (node (ref "C9") (pin "2") (pinfunction "2_2") (pintype "passive"))
      (node (ref "CF1") (pin "5") (pinfunction "5_5") (pintype "passive"))
      (node (ref "IC1") (pin "3") (pinfunction "GND_3") (pintype "power_in"))
      (node (ref "IC1") (pin "EXP") (pinfunction "GND_EXP") (pintype "power_in"))
      (node (ref "IC1") (pin "M") (pinfunction "GND_M") (pintype "power_in"))
      (node (ref "J1") (pin "3") (pinfunction "GND3_3") (pintype "passive"))
      (node (ref "J1") (pin "5") (pinfunction "GND5_5") (pintype "passive"))
      (node (ref "J1") (pin "9") (pinfunction "GND9_9") (pintype "passive"))
      (node (ref "JP1") (pin "GND") (pinfunction "1_GND") (pintype "passive"))
      (node (ref "JP10") (pin "2") (pinfunction "2_2") (pintype "passive"))
      (node (ref "JP11") (pin "2") (pinfunction "2_2") (pintype "passive"))
      (node (ref "JP2") (pin "1") (pinfunction "1_1") (pintype "passive"))
      (node (ref "JP2") (pin "2") (pinfunction "2_2") (pintype "passive"))
      (node (ref "JP3") (pin "13") (pinfunction "13_13") (pintype "passive"))
      (node (ref "JP3") (pin "14") (pinfunction "14_14") (pintype "passive"))
      (node (ref "JP5") (pin "1") (pinfunction "1_1") (pintype "passive"))
      (node (ref "JP5") (pin "2") (pinfunction "2_2") (pintype "passive"))
      (node (ref "JP6") (pin "11") (pinfunction "11_11") (pintype "passive"))
      (node (ref "JP6") (pin "12") (pinfunction "12_12") (pintype "passive"))
      (node (ref "JP8") (pin "2") (pinfunction "2_2") (pintype "passive"))
      (node (ref "R14") (pin "2") (pinfunction "2_2") (pintype "passive"))
      (node (ref "R2") (pin "1") (pinfunction "1_1") (pintype "passive"))
      (node (ref "RP1") (pin "1") (pinfunction "1_1") (pintype "passive"))
      (node (ref "RP3") (pin "1") (pinfunction "1_1") (pintype "passive"))
      (node (ref "RT1") (pin "2") (pinfunction "2_2") (pintype "passive"))
      (node (ref "S1") (pin "1") (pinfunction "O_1") (pintype "passive"))
      (node (ref "S2") (pin "B2") (pinfunction "2_B2") (pintype "passive"))
      (node (ref "TP4") (pin "P$1") (pinfunction "P$1_P$1") (pintype "bidirectional"))
      (node (ref "U$2") (pin "GND1") (pinfunction "OUTERCONDUCTOR_GND1") (pintype "bidirectional"))
      (node (ref "U$2") (pin "GND2") (pinfunction "OUTERCONDUCTOR_GND2") (pintype "bidirectional"))
      (node (ref "U$2") (pin "GND3") (pinfunction "OUTERCONDUCTOR_GND3") (pintype "bidirectional"))
      (node (ref "U$2") (pin "GND4") (pinfunction "OUTERCONDUCTOR_GND4") (pintype "bidirectional"))
      (node (ref "U1") (pin "2") (pinfunction "GND_2") (pintype "input"))
      (node (ref "U2") (pin "P$10") (pinfunction "VSS1_P$10") (pintype "power_in"))
      (node (ref "U2") (pin "P$11") (pinfunction "VSS2_P$11") (pintype "power_in"))
      (node (ref "U2") (pin "P$17") (pinfunction "CE_P$17") (pintype "input"))
      (node (ref "U2") (pin "P$21") (pinfunction "THERMAL_P$21") (pintype "power_in"))
      (node (ref "U2") (pin "P$4") (pinfunction "PROG2_P$4") (pintype "input"))
      (node (ref "U3") (pin "2") (pinfunction "VREFL_2") (pintype "input"))
      (node (ref "U3") (pin "20") (pinfunction "VSS2_20") (pintype "power_in"))
      (node (ref "U3") (pin "3") (pinfunction "VSSA_3") (pintype "power_in"))
      (node (ref "U3") (pin "36") (pinfunction "GND/SCAN_36") (pintype "power_in"))
      (node (ref "U3") (pin "38") (pinfunction "GND_PA2_38") (pintype "power_in"))
      (node (ref "U3") (pin "4") (pinfunction "VSS_4") (pintype "power_in"))
      (node (ref "U3") (pin "40") (pinfunction "GND_PA1_40") (pintype "power_in"))
      (node (ref "U3") (pin "PGND1") (pinfunction "GND1_PGND1") (pintype "power_in"))
      (node (ref "U3") (pin "PGND2") (pinfunction "GND2_PGND2") (pintype "power_in"))
    )
    (net (code "53") (name "Net-(C10-Pad1)") (class "Default")
      (node (ref "C10") (pin "1") (pinfunction "1_1") (pintype "passive"))
      (node (ref "C12") (pin "2") (pinfunction "2_2") (pintype "passive"))
      (node (ref "L2") (pin "1") (pinfunction "1_1") (pintype "passive"))
    )
    (net (code "54") (name "Net-(C12-Pad1)") (class "Default")
      (node (ref "C12") (pin "1") (pinfunction "1_1") (pintype "passive"))
      (node (ref "C13") (pin "1") (pinfunction "1_1") (pintype "passive"))
      (node (ref "L2") (pin "2") (pinfunction "2_2") (pintype "passive"))
      (node (ref "L3") (pin "1") (pinfunction "1_1") (pintype "passive"))
    )
    (net (code "55") (name "Net-(C14-Pad1)") (class "Default")
      (node (ref "C14") (pin "1") (pinfunction "1_1") (pintype "passive"))
      (node (ref "C15") (pin "1") (pinfunction "1_1") (pintype "passive"))
      (node (ref "L3") (pin "2") (pinfunction "2_2") (pintype "passive"))
    )
    (net (code "56") (name "Net-(C22-Pad1)") (class "Default")
      (node (ref "C22") (pin "1") (pinfunction "1_1") (pintype "passive"))
      (node (ref "R6") (pin "1") (pinfunction "1_1") (pintype "passive"))
      (node (ref "X1") (pin "2") (pinfunction "2_2") (pintype "passive"))
    )
    (net (code "57") (name "Net-(CF1-Pad4)") (class "Default")
      (node (ref "CF1") (pin "4") (pinfunction "4_4") (pintype "passive"))
      (node (ref "TP12") (pin "P$1") (pinfunction "P$1_P$1") (pintype "bidirectional"))
    )
    (net (code "58") (name "Net-(IC1-CTS)") (class "Default")
      (node (ref "IC1") (pin "23") (pinfunction "CTS_23") (pintype "input"))
      (node (ref "TP18") (pin "P$1") (pinfunction "P$1_P$1") (pintype "bidirectional"))
    )
    (net (code "59") (name "Net-(IC1-DCD)") (class "Default")
      (node (ref "IC1") (pin "1") (pinfunction "DCD_1") (pintype "input"))
      (node (ref "TP16") (pin "P$1") (pinfunction "P$1_P$1") (pintype "bidirectional"))
    )
    (net (code "60") (name "Net-(IC1-DSR)") (class "Default")
      (node (ref "IC1") (pin "27") (pinfunction "DSR_27") (pintype "input"))
      (node (ref "TP17") (pin "P$1") (pinfunction "P$1_P$1") (pintype "bidirectional"))
    )
    (net (code "61") (name "Net-(IC1-DTR)") (class "Default")
      (node (ref "IC1") (pin "28") (pinfunction "DTR_28") (pintype "output"))
      (node (ref "TP9") (pin "P$1") (pinfunction "P$1_P$1") (pintype "bidirectional"))
    )
    (net (code "62") (name "Net-(IC1-RI)") (class "Default")
      (node (ref "IC1") (pin "2") (pinfunction "RI_2") (pintype "input"))
      (node (ref "TP14") (pin "P$1") (pinfunction "P$1_P$1") (pintype "bidirectional"))
    )
    (net (code "63") (name "Net-(IC1-RTS)") (class "Default")
      (node (ref "IC1") (pin "24") (pinfunction "RTS_24") (pintype "output"))
      (node (ref "TP8") (pin "P$1") (pinfunction "P$1_P$1") (pintype "bidirectional"))
    )
    (net (code "64") (name "Net-(IC1-SUSPEND)") (class "Default")
      (node (ref "IC1") (pin "12") (pinfunction "SUSPEND_12") (pintype "output"))
      (node (ref "TP6") (pin "P$1") (pinfunction "P$1_P$1") (pintype "bidirectional"))
    )
    (net (code "65") (name "Net-(IC1-VDD)") (class "Default")
      (node (ref "C19") (pin "1") (pinfunction "1_1") (pintype "passive"))
      (node (ref "C24") (pin "1") (pinfunction "1_1") (pintype "passive"))
      (node (ref "IC1") (pin "6") (pinfunction "VDD_6") (pintype "power_in"))
      (node (ref "R13") (pin "1") (pinfunction "1_1") (pintype "passive"))
      (node (ref "TP13") (pin "P$1") (pinfunction "P$1_P$1") (pintype "bidirectional"))
    )
    (net (code "66") (name "Net-(IC1-~{RST})") (class "Default")
      (node (ref "IC1") (pin "9") (pinfunction "~{RST}_9") (pintype "bidirectional"))
      (node (ref "JP8") (pin "1") (pinfunction "1_1") (pintype "passive"))
      (node (ref "R13") (pin "2") (pinfunction "2_2") (pintype "passive"))
    )
    (net (code "67") (name "Net-(IC1-~{SUSPEND})") (class "Default")
      (node (ref "IC1") (pin "11") (pinfunction "~{SUSPEND}_11") (pintype "output"))
      (node (ref "TP7") (pin "P$1") (pinfunction "P$1_P$1") (pintype "bidirectional"))
    )
    (net (code "68") (name "Net-(JP5-Pad13)") (class "Default")
      (node (ref "JP5") (pin "13") (pinfunction "13_13") (pintype "passive"))
      (node (ref "JP5") (pin "14") (pinfunction "14_14") (pintype "passive"))
      (node (ref "R11") (pin "1") (pinfunction "1_1") (pintype "passive"))
    )
    (net (code "69") (name "Net-(JP6-Pad10)") (class "Default")
      (node (ref "JP6") (pin "10") (pinfunction "10_10") (pintype "passive"))
      (node (ref "JP6") (pin "9") (pinfunction "9_9") (pintype "passive"))
      (node (ref "R10") (pin "1") (pinfunction "1_1") (pintype "passive"))
    )
    (net (code "70") (name "Net-(LED1-BK)") (class "Default")
      (node (ref "LED1") (pin "1") (pinfunction "BK_1") (pintype "passive"))
      (node (ref "R5") (pin "2") (pinfunction "2_2") (pintype "passive"))
    )
    (net (code "71") (name "Net-(LED1-GK)") (class "Default")
      (node (ref "LED1") (pin "4") (pinfunction "GK_4") (pintype "passive"))
      (node (ref "R4") (pin "2") (pinfunction "2_2") (pintype "passive"))
    )
    (net (code "72") (name "Net-(LED1-RK)") (class "Default")
      (node (ref "LED1") (pin "3") (pinfunction "RK_3") (pintype "passive"))
      (node (ref "R3") (pin "2") (pinfunction "2_2") (pintype "passive"))
    )
    (net (code "73") (name "Net-(LED2-BK)") (class "Default")
      (node (ref "LED2") (pin "1") (pinfunction "BK_1") (pintype "passive"))
      (node (ref "R9") (pin "1") (pinfunction "1_1") (pintype "passive"))
    )
    (net (code "74") (name "Net-(LED2-GK)") (class "Default")
      (node (ref "LED2") (pin "4") (pinfunction "GK_4") (pintype "passive"))
      (node (ref "R8") (pin "1") (pinfunction "1_1") (pintype "passive"))
    )
    (net (code "75") (name "Net-(LED2-RK)") (class "Default")
      (node (ref "LED2") (pin "3") (pinfunction "RK_3") (pintype "passive"))
      (node (ref "R7") (pin "1") (pinfunction "1_1") (pintype "passive"))
    )
    (net (code "76") (name "Net-(LED3-PadK)") (class "Default")
      (node (ref "LED3") (pin "K") (pinfunction "K_K") (pintype "passive"))
      (node (ref "R2") (pin "2") (pinfunction "2_2") (pintype "passive"))
    )
    (net (code "77") (name "Net-(S1-P)") (class "Default")
      (node (ref "S1") (pin "2") (pinfunction "P_2") (pintype "passive"))
      (node (ref "U1") (pin "3") (pinfunction "EN_3") (pintype "input"))
    )
    (net (code "78") (name "Net-(U$2-CENTERCONDUCTOR)") (class "Default")
      (node (ref "C15") (pin "2") (pinfunction "2_2") (pintype "passive"))
      (node (ref "U$2") (pin "P$3") (pinfunction "CENTERCONDUCTOR_P$3") (pintype "bidirectional"))
    )
    (net (code "79") (name "Net-(U1-BP)") (class "Default")
      (node (ref "C7") (pin "1") (pinfunction "1_1") (pintype "passive"))
      (node (ref "U1") (pin "4") (pinfunction "BP_4") (pintype "input"))
    )
    (net (code "80") (name "Net-(U2-PROG1)") (class "Default")
      (node (ref "RP1") (pin "2") (pinfunction "2_2") (pintype "passive"))
      (node (ref "U2") (pin "P$13") (pinfunction "PROG1_P$13") (pintype "passive"))
    )
    (net (code "81") (name "Net-(U2-PROG3)") (class "Default")
      (node (ref "RP3") (pin "2") (pinfunction "2_2") (pintype "passive"))
      (node (ref "U2") (pin "P$12") (pinfunction "PROG3_P$12") (pintype "passive"))
    )
    (net (code "82") (name "Net-(U2-THERM)") (class "Default")
      (node (ref "RT1") (pin "1") (pinfunction "1_1") (pintype "passive"))
      (node (ref "U2") (pin "P$5") (pinfunction "THERM_P$5") (pintype "passive"))
    )
    (net (code "83") (name "Net-(U3-PA_BOOST)") (class "Default")
      (node (ref "TP10") (pin "P$1") (pinfunction "P$1_P$1") (pintype "bidirectional"))
      (node (ref "U3") (pin "41") (pinfunction "PA_BOOST_41") (pintype "output"))
    )
    (net (code "84") (name "Net-(U3-RXTX)") (class "Default")
      (node (ref "TP11") (pin "P$1") (pinfunction "P$1_P$1") (pintype "bidirectional"))
      (node (ref "U3") (pin "37") (pinfunction "RXTX_37") (pintype "output"))
    )
    (net (code "85") (name "Net-(U3-VR_ANA)") (class "Default")
      (node (ref "C25") (pin "1") (pinfunction "1_1") (pintype "passive"))
      (node (ref "U3") (pin "44") (pinfunction "VR_ANA_44") (pintype "output"))
    )
    (net (code "86") (name "Net-(U3-VR_DIG)") (class "Default")
      (node (ref "C23") (pin "1") (pinfunction "1_1") (pintype "passive"))
      (node (ref "U3") (pin "45") (pinfunction "VR_DIG_45") (pintype "output"))
    )
    (net (code "87") (name "V+") (class "Default")
      (node (ref "C4") (pin "1") (pinfunction "1_1") (pintype "passive"))
      (node (ref "JP1") (pin "VCC") (pinfunction "2_VCC") (pintype "passive"))
      (node (ref "JP10") (pin "1") (pinfunction "1_1") (pintype "passive"))
      (node (ref "TP1") (pin "P$1") (pinfunction "P$1_P$1") (pintype "bidirectional"))
      (node (ref "U2") (pin "P$14") (pinfunction "VBAT1_P$14") (pintype "power_in"))
      (node (ref "U2") (pin "P$15") (pinfunction "VBAT2_P$15") (pintype "power_in"))
      (node (ref "U2") (pin "P$16") (pinfunction "VBATSENS_P$16") (pintype "passive"))
    )
    (net (code "88") (name "unconnected-(J1-RTCK-Pad7)") (class "Default")
      (node (ref "J1") (pin "7") (pinfunction "RTCK_7") (pintype "passive"))
    )
    (net (code "89") (name "unconnected-(J1-TDI-Pad8)") (class "Default")
      (node (ref "J1") (pin "8") (pinfunction "TDI_8") (pintype "passive"))
    )
    (net (code "90") (name "unconnected-(J1-TDO-Pad6)") (class "Default")
      (node (ref "J1") (pin "6") (pinfunction "TDO_6") (pintype "passive"))
    )
    (net (code "91") (name "unconnected-(U3-NC-Pad30)") (class "Default")
      (node (ref "U3") (pin "30") (pinfunction "NC_30") (pintype "no_connect"))
    )
  )
)
